# CE_BJTInfineonSOT343_v1.net
KiCad netlist of a schematic drawn in Altium Designer
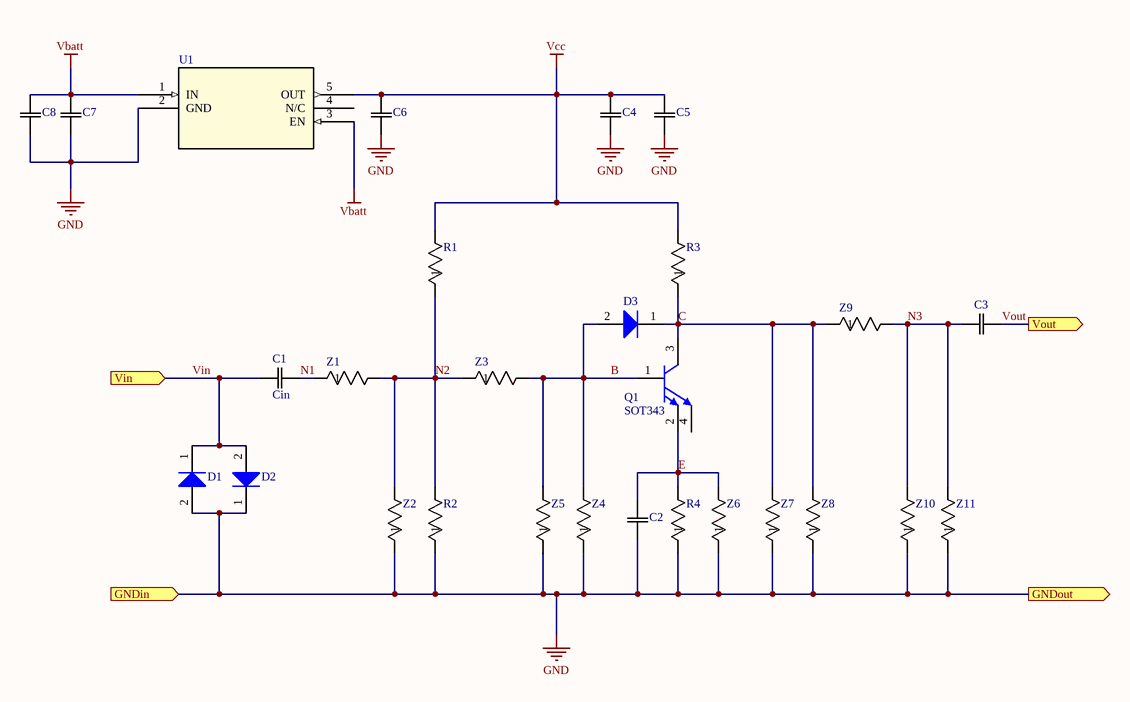
[diagram p0: CE_BJTInfineonSOT343_v1.SchDoc]

(export (version "E")
  (design (tool "Eeschema 10.0.6"))
  (components
    (comp (ref "C1")
      (value "Cin")
      (footprint "C0201")
      (description "No Description Available")
      (fields
        (field (name "MANUFACTURER_PART_NUMBER") "C0201C270J3GACTU")
        (field (name "COPYRIGHT") "Copyright (C) 2018 Accelerated Designs. All rights reserved")
      )
      (libsource (lib "0201Capacitor_Yageo") (part "C0201C270J3GACTU"))
    )
    (comp (ref "C2")
      (value "~")
      (footprint "C0201")
      (description "No Description Available")
      (fields
        (field (name "MANUFACTURER_PART_NUMBER") "C0201C270J3GACTU")
        (field (name "COPYRIGHT") "Copyright (C) 2018 Accelerated Designs. All rights reserved")
      )
      (libsource (lib "0201Capacitor_Yageo") (part "C0201C270J3GACTU"))
    )
    (comp (ref "C3")
      (value "~")
      (footprint "C0201")
      (description "No Description Available")
      (fields
        (field (name "MANUFACTURER_PART_NUMBER") "C0201C270J3GACTU")
        (field (name "COPYRIGHT") "Copyright (C) 2018 Accelerated Designs. All rights reserved")
      )
      (libsource (lib "0201Capacitor_Yageo") (part "C0201C270J3GACTU"))
    )
    (comp (ref "C4")
      (value "~")
      (footprint "CAP_CBR_0201")
      (description "No Description Available")
      (fields
        (field (name "MANUFACTURER_PART_NUMBER") "CBR02C399C3GAC")
        (field (name "COPYRIGHT") "Copyright (C) 2018 Accelerated Designs. All rights reserved")
      )
      (libsource (lib "0201Capacitor_KEMET") (part "CBR02C399C3GAC"))
    )
    (comp (ref "C5")
      (value "~")
      (footprint "CAP_CBR_0201")
      (description "No Description Available")
      (fields
        (field (name "MANUFACTURER_PART_NUMBER") "CBR02C399C3GAC")
        (field (name "COPYRIGHT") "Copyright (C) 2018 Accelerated Designs. All rights reserved")
      )
      (libsource (lib "0201Capacitor_KEMET") (part "CBR02C399C3GAC"))
    )
    (comp (ref "C6")
      (value "~")
      (footprint "YAG_CC0402")
      (description "No Description Available")
      (fields
        (field (name "MANUFACTURER_PART_NUMBER") "CC0402KRX7R9BB103")
        (field (name "COPYRIGHT") "Copyright (C) 2018 Accelerated Designs. All rights reserved")
      )
      (libsource (lib "0402Capacitor_Yageo") (part "CC0402KRX7R9BB10"))
    )
    (comp (ref "C7")
      (value "~")
      (footprint "YAG_CC0402")
      (description "No Description Available")
      (fields
        (field (name "MANUFACTURER_PART_NUMBER") "CC0402KRX7R9BB103")
        (field (name "COPYRIGHT") "Copyright (C) 2018 Accelerated Designs. All rights reserved")
      )
      (libsource (lib "0402Capacitor_Yageo") (part "CC0402KRX7R9BB10"))
    )
    (comp (ref "C8")
      (value "~")
      (footprint "YAG_CC0402")
      (description "No Description Available")
      (fields
        (field (name "MANUFACTURER_PART_NUMBER") "CC0402KRX7R9BB103")
        (field (name "COPYRIGHT") "Copyright (C) 2018 Accelerated Designs. All rights reserved")
      )
      (libsource (lib "0402Capacitor_Yageo") (part "CC0402KRX7R9BB10"))
    )
    (comp (ref "D1")
      (value "~")
      (footprint "INF-SOD323_V")
      (description "Single Silicon Schottky Diode, 110 mA IF Max, SOD32, Green")
      (fields (field (name "MANUFACTURER") "Infineon") (field (name "PARTNUMBER") "BAT15-03W"))
      (libsource (lib "Infineon_RFSchottkyDiode_SOD323") (part "BAT15-03W"))
    )
    (comp (ref "D2")
      (value "~")
      (footprint "INF-SOD323_V")
      (description "Single Silicon Schottky Diode, 110 mA IF Max, SOD32, Green")
      (fields (field (name "MANUFACTURER") "Infineon") (field (name "PARTNUMBER") "BAT15-03W"))
      (libsource (lib "Infineon_RFSchottkyDiode_SOD323") (part "BAT15-03W"))
    )
    (comp (ref "D3")
      (value "~")
      (footprint "INF-SOD323_V")
      (description "Single Silicon Schottky Diode, 110 mA IF Max, SOD32, Green")
      (fields (field (name "MANUFACTURER") "Infineon") (field (name "PARTNUMBER") "BAT15-03W"))
      (libsource (lib "Infineon_RFSchottkyDiode_SOD323") (part "BAT15-03W"))
    )
    (comp (ref "Q1")
      (value "SOT343")
      (footprint "INF-SOT343_V")
      (fields (field (name "MANUFACTURER") "Infineon") (field (name "PARTNUMBER") "BFP840ESD"))
      (libsource (lib "Infineon_RFBJT_SOT343") (part "BFP840ESD"))
    )
    (comp (ref "R1")
      (value "~")
      (footprint "RES_RC0201_P6XP3")
      (description "No Description Available")
      (fields
        (field (name "MANUFACTURER_PART_NUMBER") "RC0201FR-0718KL")
        (field (name "COPYRIGHT") "Copyright (C) 2018 Accelerated Designs. All rights reserved")
      )
      (libsource (lib "0201Resistor_Yageo") (part "RC0201FR-0718KL"))
    )
    (comp (ref "R2")
      (value "~")
      (footprint "RES_RC0201_P6XP3")
      (description "No Description Available")
      (fields
        (field (name "MANUFACTURER_PART_NUMBER") "RC0201FR-0718KL")
        (field (name "COPYRIGHT") "Copyright (C) 2018 Accelerated Designs. All rights reserved")
      )
      (libsource (lib "0201Resistor_Yageo") (part "RC0201FR-0718KL"))
    )
    (comp (ref "R3")
      (value "~")
      (footprint "RES_RC0201_P6XP3")
      (description "No Description Available")
      (fields
        (field (name "MANUFACTURER_PART_NUMBER") "RC0201FR-0718KL")
        (field (name "COPYRIGHT") "Copyright (C) 2018 Accelerated Designs. All rights reserved")
      )
      (libsource (lib "0201Resistor_Yageo") (part "RC0201FR-0718KL"))
    )
    (comp (ref "R4")
      (value "~")
      (footprint "RES_RC0201_P6XP3")
      (description "No Description Available")
      (fields
        (field (name "MANUFACTURER_PART_NUMBER") "RC0201FR-0718KL")
        (field (name "COPYRIGHT") "Copyright (C) 2018 Accelerated Designs. All rights reserved")
      )
      (libsource (lib "0201Resistor_Yageo") (part "RC0201FR-0718KL"))
    )
    (comp (ref "U1")
      (value "~")
      (footprint "DBV5")
      (description "No Description Available")
      (fields
        (field (name "MANUFACTURER_PART_NUMBER") "LP5907MFX-3.3/NOPB")
        (field (name "COPYRIGHT") "Copyright (C) 2018 Accelerated Designs. All rights reserved")
      )
      (libsource (lib "TI_LDO_3V3_SOT325") (part "LP5907MFX-3.3/NO"))
    )
    (comp (ref "Z1")
      (value "~")
      (footprint "RES_RC0201_P6XP3")
      (description "No Description Available")
      (fields
        (field (name "MANUFACTURER_PART_NUMBER") "RC0201FR-0718KL")
        (field (name "COPYRIGHT") "Copyright (C) 2018 Accelerated Designs. All rights reserved")
      )
      (libsource (lib "0201Resistor_Yageo") (part "RC0201FR-0718KL"))
    )
    (comp (ref "Z2")
      (value "~")
      (footprint "RES_RC0201_P6XP3")
      (description "No Description Available")
      (fields
        (field (name "MANUFACTURER_PART_NUMBER") "RC0201FR-0718KL")
        (field (name "COPYRIGHT") "Copyright (C) 2018 Accelerated Designs. All rights reserved")
      )
      (libsource (lib "0201Resistor_Yageo") (part "RC0201FR-0718KL"))
    )
    (comp (ref "Z3")
      (value "~")
      (footprint "RES_RC0201_P6XP3")
      (description "No Description Available")
      (fields
        (field (name "MANUFACTURER_PART_NUMBER") "RC0201FR-0718KL")
        (field (name "COPYRIGHT") "Copyright (C) 2018 Accelerated Designs. All rights reserved")
      )
      (libsource (lib "0201Resistor_Yageo") (part "RC0201FR-0718KL"))
    )
    (comp (ref "Z4")
      (value "~")
      (footprint "RES_RC0201_P6XP3")
      (description "No Description Available")
      (fields
        (field (name "MANUFACTURER_PART_NUMBER") "RC0201FR-0718KL")
        (field (name "COPYRIGHT") "Copyright (C) 2018 Accelerated Designs. All rights reserved")
      )
      (libsource (lib "0201Resistor_Yageo") (part "RC0201FR-0718KL"))
    )
    (comp (ref "Z5")
      (value "~")
      (footprint "RES_RC0201_P6XP3")
      (description "No Description Available")
      (fields
        (field (name "MANUFACTURER_PART_NUMBER") "RC0201FR-0718KL")
        (field (name "COPYRIGHT") "Copyright (C) 2018 Accelerated Designs. All rights reserved")
      )
      (libsource (lib "0201Resistor_Yageo") (part "RC0201FR-0718KL"))
    )
    (comp (ref "Z6")
      (value "~")
      (footprint "RES_RC0201_P6XP3")
      (description "No Description Available")
      (fields
        (field (name "MANUFACTURER_PART_NUMBER") "RC0201FR-0718KL")
        (field (name "COPYRIGHT") "Copyright (C) 2018 Accelerated Designs. All rights reserved")
      )
      (libsource (lib "0201Resistor_Yageo") (part "RC0201FR-0718KL"))
    )
    (comp (ref "Z7")
      (value "~")
      (footprint "RES_RC0201_P6XP3")
      (description "No Description Available")
      (fields
        (field (name "MANUFACTURER_PART_NUMBER") "RC0201FR-0718KL")
        (field (name "COPYRIGHT") "Copyright (C) 2018 Accelerated Designs. All rights reserved")
      )
      (libsource (lib "0201Resistor_Yageo") (part "RC0201FR-0718KL"))
    )
    (comp (ref "Z8")
      (value "~")
      (footprint "RES_RC0201_P6XP3")
      (description "No Description Available")
      (fields
        (field (name "MANUFACTURER_PART_NUMBER") "RC0201FR-0718KL")
        (field (name "COPYRIGHT") "Copyright (C) 2018 Accelerated Designs. All rights reserved")
      )
      (libsource (lib "0201Resistor_Yageo") (part "RC0201FR-0718KL"))
    )
    (comp (ref "Z9")
      (value "~")
      (footprint "RES_RC0201_P6XP3")
      (description "No Description Available")
      (fields
        (field (name "MANUFACTURER_PART_NUMBER") "RC0201FR-0718KL")
        (field (name "COPYRIGHT") "Copyright (C) 2018 Accelerated Designs. All rights reserved")
      )
      (libsource (lib "0201Resistor_Yageo") (part "RC0201FR-0718KL"))
    )
    (comp (ref "Z10")
      (value "~")
      (footprint "RES_RC0201_P6XP3")
      (description "No Description Available")
      (fields
        (field (name "MANUFACTURER_PART_NUMBER") "RC0201FR-0718KL")
        (field (name "COPYRIGHT") "Copyright (C) 2018 Accelerated Designs. All rights reserved")
      )
      (libsource (lib "0201Resistor_Yageo") (part "RC0201FR-0718KL"))
    )
    (comp (ref "Z11")
      (value "~")
      (footprint "RES_RC0201_P6XP3")
      (description "No Description Available")
      (fields
        (field (name "MANUFACTURER_PART_NUMBER") "RC0201FR-0718KL")
        (field (name "COPYRIGHT") "Copyright (C) 2018 Accelerated Designs. All rights reserved")
      )
      (libsource (lib "0201Resistor_Yageo") (part "RC0201FR-0718KL"))
    )
  )
  (nets
    (net (code "1") (name "/B") (class "Default")
      (node (ref "D3") (pin "2") (pinfunction "A_2") (pintype "passive"))
      (node (ref "Q1") (pin "1") (pinfunction "B_1") (pintype "passive"))
      (node (ref "Z3") (pin "2") (pinfunction "2_2") (pintype "passive"))
      (node (ref "Z4") (pin "2") (pinfunction "2_2") (pintype "passive"))
      (node (ref "Z5") (pin "2") (pinfunction "2_2") (pintype "passive"))
    )
    (net (code "2") (name "/C") (class "Default")
      (node (ref "D3") (pin "1") (pinfunction "K_1") (pintype "passive"))
      (node (ref "Q1") (pin "3") (pinfunction "C_3") (pintype "passive"))
      (node (ref "R3") (pin "1") (pinfunction "1_1") (pintype "passive"))
      (node (ref "Z7") (pin "2") (pinfunction "2_2") (pintype "passive"))
      (node (ref "Z8") (pin "2") (pinfunction "2_2") (pintype "passive"))
      (node (ref "Z9") (pin "1") (pinfunction "1_1") (pintype "passive"))
    )
    (net (code "3") (name "/E") (class "Default")
      (node (ref "C2") (pin "2") (pinfunction "2_2") (pintype "passive"))
      (node (ref "Q1") (pin "2") (pinfunction "E_2") (pintype "passive"))
      (node (ref "R4") (pin "2") (pinfunction "2_2") (pintype "passive"))
      (node (ref "Z6") (pin "2") (pinfunction "2_2") (pintype "passive"))
    )
    (net (code "4") (name "/N1") (class "Default")
      (node (ref "C1") (pin "2") (pinfunction "2_2") (pintype "passive"))
      (node (ref "Z1") (pin "1") (pinfunction "1_1") (pintype "passive"))
    )
    (net (code "5") (name "/N2") (class "Default")
      (node (ref "R1") (pin "1") (pinfunction "1_1") (pintype "passive"))
      (node (ref "R2") (pin "2") (pinfunction "2_2") (pintype "passive"))
      (node (ref "Z1") (pin "2") (pinfunction "2_2") (pintype "passive"))
      (node (ref "Z2") (pin "2") (pinfunction "2_2") (pintype "passive"))
      (node (ref "Z3") (pin "1") (pinfunction "1_1") (pintype "passive"))
    )
    (net (code "6") (name "/N3") (class "Default")
      (node (ref "C3") (pin "1") (pinfunction "1_1") (pintype "passive"))
      (node (ref "Z10") (pin "2") (pinfunction "2_2") (pintype "passive"))
      (node (ref "Z11") (pin "2") (pinfunction "2_2") (pintype "passive"))
      (node (ref "Z9") (pin "2") (pinfunction "2_2") (pintype "passive"))
    )
    (net (code "7") (name "/Vin") (class "Default")
      (node (ref "C1") (pin "1") (pinfunction "1_1") (pintype "passive"))
      (node (ref "D1") (pin "1") (pinfunction "K_1") (pintype "passive"))
      (node (ref "D2") (pin "2") (pinfunction "A_2") (pintype "passive"))
    )
    (net (code "8") (name "/Vout") (class "Default")
      (node (ref "C3") (pin "2") (pinfunction "2_2") (pintype "passive"))
    )
    (net (code "9") (name "GND") (class "Default")
      (node (ref "C2") (pin "1") (pinfunction "1_1") (pintype "passive"))
      (node (ref "C4") (pin "1") (pinfunction "1_1") (pintype "passive"))
      (node (ref "C5") (pin "1") (pinfunction "1_1") (pintype "passive"))
      (node (ref "C6") (pin "1") (pinfunction "1_1") (pintype "passive"))
      (node (ref "C7") (pin "1") (pinfunction "1_1") (pintype "passive"))
      (node (ref "C8") (pin "1") (pinfunction "1_1") (pintype "passive"))
      (node (ref "D1") (pin "2") (pinfunction "A_2") (pintype "passive"))
      (node (ref "D2") (pin "1") (pinfunction "K_1") (pintype "passive"))
      (node (ref "R2") (pin "1") (pinfunction "1_1") (pintype "passive"))
      (node (ref "R4") (pin "1") (pinfunction "1_1") (pintype "passive"))
      (node (ref "U1") (pin "2") (pinfunction "GND_2") (pintype "power_in"))
      (node (ref "Z10") (pin "1") (pinfunction "1_1") (pintype "passive"))
      (node (ref "Z11") (pin "1") (pinfunction "1_1") (pintype "passive"))
      (node (ref "Z2") (pin "1") (pinfunction "1_1") (pintype "passive"))
      (node (ref "Z4") (pin "1") (pinfunction "1_1") (pintype "passive"))
      (node (ref "Z5") (pin "1") (pinfunction "1_1") (pintype "passive"))
      (node (ref "Z6") (pin "1") (pinfunction "1_1") (pintype "passive"))
      (node (ref "Z7") (pin "1") (pinfunction "1_1") (pintype "passive"))
      (node (ref "Z8") (pin "1") (pinfunction "1_1") (pintype "passive"))
    )
    (net (code "10") (name "Vbatt") (class "Default")
      (node (ref "C7") (pin "2") (pinfunction "2_2") (pintype "passive"))
      (node (ref "C8") (pin "2") (pinfunction "2_2") (pintype "passive"))
      (node (ref "U1") (pin "1") (pinfunction "IN_1") (pintype "input"))
      (node (ref "U1") (pin "3") (pinfunction "EN_3") (pintype "input"))
    )
    (net (code "11") (name "Vcc") (class "Default")
      (node (ref "C4") (pin "2") (pinfunction "2_2") (pintype "passive"))
      (node (ref "C5") (pin "2") (pinfunction "2_2") (pintype "passive"))
      (node (ref "C6") (pin "2") (pinfunction "2_2") (pintype "passive"))
      (node (ref "R1") (pin "2") (pinfunction "2_2") (pintype "passive"))
      (node (ref "R3") (pin "2") (pinfunction "2_2") (pintype "passive"))
      (node (ref "U1") (pin "5") (pinfunction "OUT_5") (pintype "output"))
    )
    (net (code "12") (name "unconnected-(Q1-E-Pad4)") (class "Default")
      (node (ref "Q1") (pin "4") (pinfunction "E_4") (pintype "passive"))
    )
    (net (code "13") (name "unconnected-(U1-N{slash}C-Pad4)") (class "Default")
      (node (ref "U1") (pin "4") (pinfunction "N/C_4") (pintype "passive"))
    )
  )
)
